# mos.net
KiCad netlist of a schematic drawn in Altium Designer
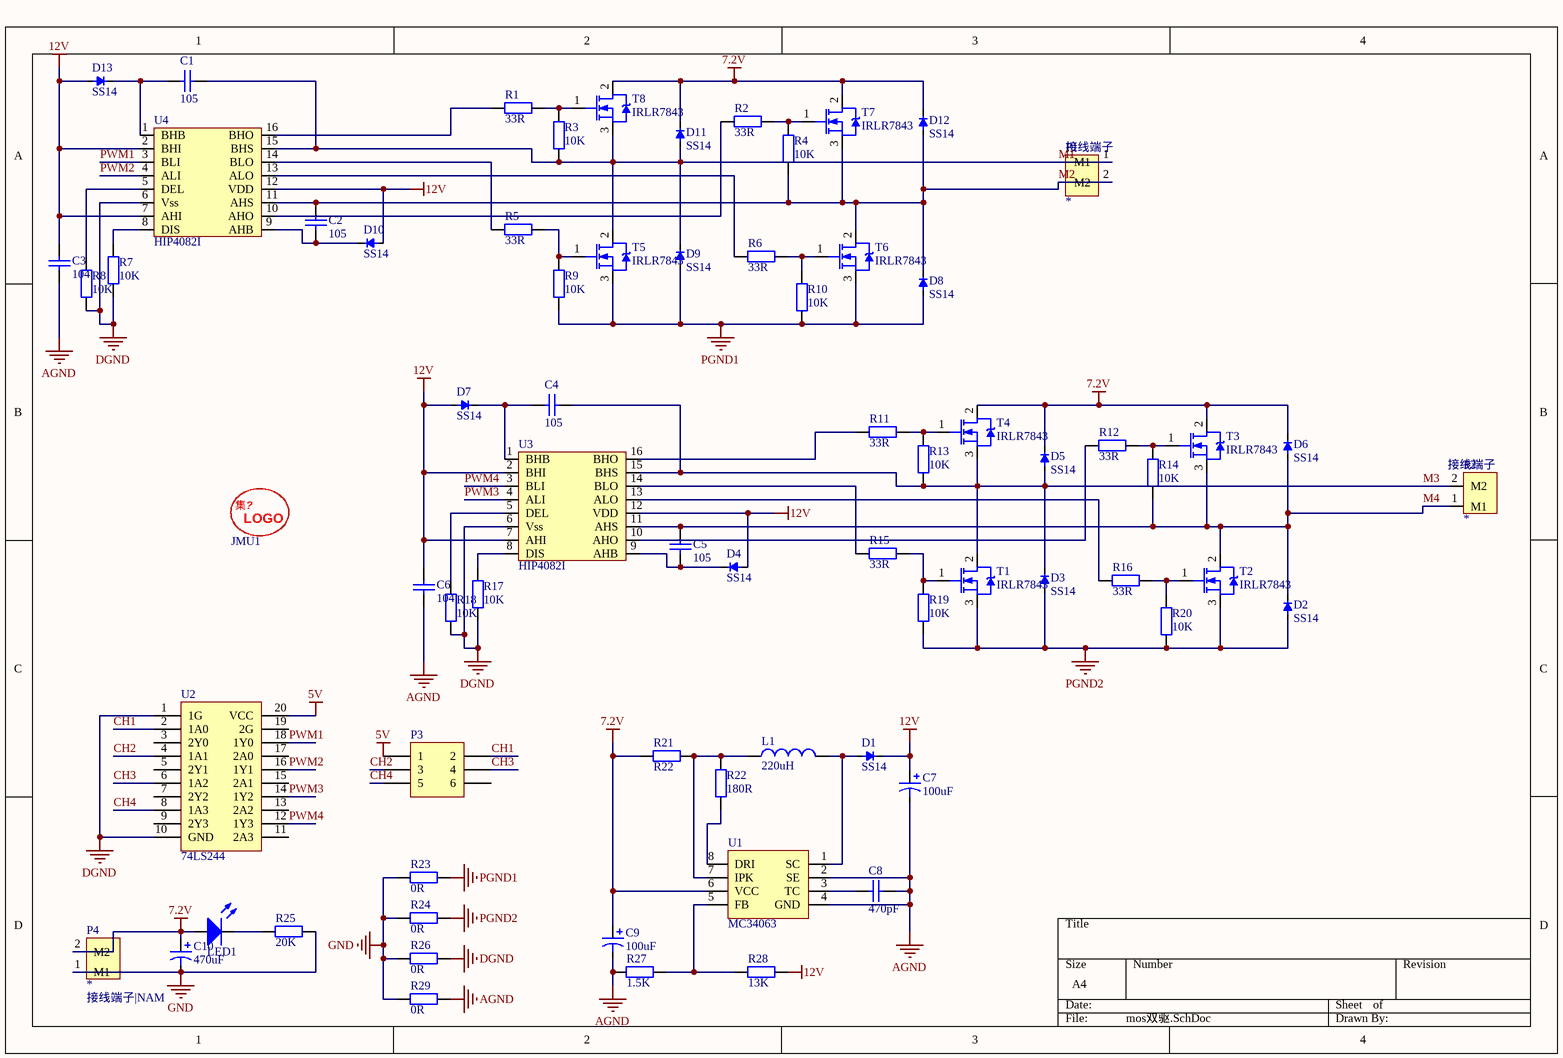
[diagram p0: mos双驱.SchDoc]

(export (version "E")
  (design (tool "Eeschema 10.0.6"))
  (components
    (comp (ref "C1")
      (value "105")
      (footprint "0805")
      (description "无极电容")
      (libsource (lib "JMU智能车专用2.0.8") (part "Cap"))
    )
    (comp (ref "C2")
      (value "105")
      (footprint "0805")
      (description "无极电容")
      (libsource (lib "JMU智能车专用2.0.8") (part "Cap"))
    )
    (comp (ref "C3")
      (value "104")
      (footprint "0805")
      (description "无极电容")
      (libsource (lib "JMU智能车专用2.0.8") (part "Cap"))
    )
    (comp (ref "C4")
      (value "105")
      (footprint "0805")
      (description "无极电容")
      (libsource (lib "JMU智能车专用2.0.8") (part "Cap"))
    )
    (comp (ref "C5")
      (value "105")
      (footprint "0805")
      (description "无极电容")
      (libsource (lib "JMU智能车专用2.0.8") (part "Cap"))
    )
    (comp (ref "C6")
      (value "104")
      (footprint "0805")
      (description "无极电容")
      (libsource (lib "JMU智能车专用2.0.8") (part "Cap"))
    )
    (comp (ref "C7")
      (value "100uF")
      (footprint "ED6.3")
      (description "通用有极电容")
      (libsource (lib "JMU智能车专用2.0.8") (part "pol cap"))
    )
    (comp (ref "C8")
      (value "470pF")
      (footprint "0805")
      (description "无极电容")
      (libsource (lib "JMU智能车专用2.0.8") (part "Cap"))
    )
    (comp (ref "C9")
      (value "100uF")
      (footprint "Pol Cap(220uF)")
      (description "通用有极电容")
      (libsource (lib "JMU智能车专用2.0.8") (part "pol cap"))
    )
    (comp (ref "C10")
      (value "470uF")
      (footprint "ED8")
      (description "ED8:470UF  ED6.3:100UF")
      (libsource (lib "JMU智能车专用2.0.8") (part "固态贴片电容"))
    )
    (comp (ref "D1") (value "SS14") (footprint "二极管") (libsource (lib "JMU智能车专用2.0.8") (part "IN5819")))
    (comp (ref "D2") (value "SS14") (footprint "二极管") (libsource (lib "JMU智能车专用2.0.8") (part "IN5819")))
    (comp (ref "D3") (value "SS14") (footprint "二极管") (libsource (lib "JMU智能车专用2.0.8") (part "IN5819")))
    (comp (ref "D4") (value "SS14") (footprint "二极管") (libsource (lib "JMU智能车专用2.0.8") (part "IN5819")))
    (comp (ref "D5") (value "SS14") (footprint "二极管") (libsource (lib "JMU智能车专用2.0.8") (part "IN5819")))
    (comp (ref "D6") (value "SS14") (footprint "二极管") (libsource (lib "JMU智能车专用2.0.8") (part "IN5819")))
    (comp (ref "D7") (value "SS14") (footprint "二极管") (libsource (lib "JMU智能车专用2.0.8") (part "IN5819")))
    (comp (ref "D8") (value "SS14") (footprint "二极管") (libsource (lib "JMU智能车专用2.0.8") (part "IN5819")))
    (comp (ref "D9") (value "SS14") (footprint "二极管") (libsource (lib "JMU智能车专用2.0.8") (part "IN5819")))
    (comp (ref "D10") (value "SS14") (footprint "二极管") (libsource (lib "JMU智能车专用2.0.8") (part "IN5819")))
    (comp (ref "D11") (value "SS14") (footprint "二极管") (libsource (lib "JMU智能车专用2.0.8") (part "IN5819")))
    (comp (ref "D12") (value "SS14") (footprint "二极管") (libsource (lib "JMU智能车专用2.0.8") (part "IN5819")))
    (comp (ref "D13") (value "SS14") (footprint "二极管") (libsource (lib "JMU智能车专用2.0.8") (part "IN5819")))
    (comp (ref "JMU1")
      (value "JMU")
      (footprint "JMU_logo（1）")
      (libsource (lib "JMU智能车专用2.0.8") (part "JMU-LOGO"))
    )
    (comp (ref "L1")
      (value "220uH")
      (footprint "电感（220uh）")
      (description "7*7*4")
      (libsource (lib "JMU智能车专用2.0.8") (part "电感 220uh"))
    )
    (comp (ref "LED1")
      (value "LED")
      (footprint "LED(0805)")
      (description "发光二极管")
      (libsource (lib "JMU智能车专用2.0.8") (part "LED"))
    )
    (comp (ref "P1") (value "*") (footprint "接线端子") (libsource (lib "") (part "接线端子_1")))
    (comp (ref "P2") (value "*") (footprint "接线端子") (libsource (lib "JMU智能车专用2.0.8") (part "接线端子")))
    (comp (ref "P3")
      (value "Header 3X2")
      (footprint "HDR2X3")
      (description "Header, 3-Pin, Dual row")
      (fields (field (name "PUBLISHER") "Altium Limited"))
      (libsource (lib "Miscellaneous Connectors") (part "Header 3X2"))
    )
    (comp (ref "P4")
      (value "*")
      (footprint "接线端子")
      (fields (field (name "ALTIUM_UNNAMED_3") "接线端子"))
      (libsource (lib "JMU智能车专用2.0.8") (part "接线端子"))
    )
    (comp (ref "R1")
      (value "33R")
      (footprint "0603")
      (description "通用电阻")
      (libsource (lib "") (part "Res_2"))
    )
    (comp (ref "R2")
      (value "33R")
      (footprint "0603")
      (description "通用电阻")
      (libsource (lib "") (part "Res_2"))
    )
    (comp (ref "R3")
      (value "10K")
      (footprint "0603")
      (description "通用电阻")
      (libsource (lib "JMU智能车专用2.0.8") (part "Res"))
    )
    (comp (ref "R4")
      (value "10K")
      (footprint "0603")
      (description "通用电阻")
      (libsource (lib "JMU智能车专用2.0.8") (part "Res"))
    )
    (comp (ref "R5")
      (value "33R")
      (footprint "0603")
      (description "通用电阻")
      (libsource (lib "") (part "Res_2"))
    )
    (comp (ref "R6")
      (value "33R")
      (footprint "0603")
      (description "通用电阻")
      (libsource (lib "") (part "Res_2"))
    )
    (comp (ref "R7")
      (value "10K")
      (footprint "0603")
      (description "通用电阻")
      (libsource (lib "JMU智能车专用2.0.8") (part "Res"))
    )
    (comp (ref "R8")
      (value "10K")
      (footprint "0603")
      (description "通用电阻")
      (libsource (lib "JMU智能车专用2.0.8") (part "Res"))
    )
    (comp (ref "R9")
      (value "10K")
      (footprint "0603")
      (description "通用电阻")
      (libsource (lib "JMU智能车专用2.0.8") (part "Res"))
    )
    (comp (ref "R10")
      (value "10K")
      (footprint "0603")
      (description "通用电阻")
      (libsource (lib "JMU智能车专用2.0.8") (part "Res"))
    )
    (comp (ref "R11")
      (value "33R")
      (footprint "0603")
      (description "通用电阻")
      (libsource (lib "") (part "Res_2"))
    )
    (comp (ref "R12")
      (value "33R")
      (footprint "0603")
      (description "通用电阻")
      (libsource (lib "") (part "Res_2"))
    )
    (comp (ref "R13")
      (value "10K")
      (footprint "0603")
      (description "通用电阻")
      (libsource (lib "JMU智能车专用2.0.8") (part "Res"))
    )
    (comp (ref "R14")
      (value "10K")
      (footprint "0603")
      (description "通用电阻")
      (libsource (lib "JMU智能车专用2.0.8") (part "Res"))
    )
    (comp (ref "R15")
      (value "33R")
      (footprint "0603")
      (description "通用电阻")
      (libsource (lib "") (part "Res_2"))
    )
    (comp (ref "R16")
      (value "33R")
      (footprint "0603")
      (description "通用电阻")
      (libsource (lib "") (part "Res_2"))
    )
    (comp (ref "R17")
      (value "10K")
      (footprint "0603")
      (description "通用电阻")
      (libsource (lib "JMU智能车专用2.0.8") (part "Res"))
    )
    (comp (ref "R18")
      (value "10K")
      (footprint "0603")
      (description "通用电阻")
      (libsource (lib "JMU智能车专用2.0.8") (part "Res"))
    )
    (comp (ref "R19")
      (value "10K")
      (footprint "0603")
      (description "通用电阻")
      (libsource (lib "JMU智能车专用2.0.8") (part "Res"))
    )
    (comp (ref "R20")
      (value "10K")
      (footprint "0603")
      (description "通用电阻")
      (libsource (lib "JMU智能车专用2.0.8") (part "Res"))
    )
    (comp (ref "R21")
      (value "R22")
      (footprint "0805")
      (description "通用电阻")
      (libsource (lib "") (part "Res_2"))
    )
    (comp (ref "R22")
      (value "180R")
      (footprint "0805")
      (description "通用电阻")
      (libsource (lib "JMU智能车专用2.0.8") (part "Res"))
    )
    (comp (ref "R23")
      (value "0R")
      (footprint "0805")
      (description "通用电阻")
      (libsource (lib "") (part "Res_1"))
    )
    (comp (ref "R24")
      (value "0R")
      (footprint "0805")
      (description "通用电阻")
      (libsource (lib "") (part "Res_1"))
    )
    (comp (ref "R25")
      (value "20K")
      (footprint "0805")
      (description "通用电阻")
      (libsource (lib "") (part "Res_1"))
    )
    (comp (ref "R26")
      (value "0R")
      (footprint "0805")
      (description "通用电阻")
      (libsource (lib "") (part "Res_1"))
    )
    (comp (ref "R27")
      (value "1.5K")
      (footprint "0805")
      (description "通用电阻")
      (libsource (lib "") (part "Res_1"))
    )
    (comp (ref "R28")
      (value "13K")
      (footprint "0805")
      (description "通用电阻")
      (libsource (lib "") (part "Res_1"))
    )
    (comp (ref "R29")
      (value "0R")
      (footprint "0805")
      (description "通用电阻")
      (libsource (lib "") (part "Res_1"))
    )
    (comp (ref "T1")
      (value "IRLR7843")
      (footprint "IRLR7843(MOS)")
      (libsource (lib "JMU智能车专用2.0.8") (part "N_MOS(IRLR7843)"))
    )
    (comp (ref "T2")
      (value "IRLR7843")
      (footprint "IRLR7843(MOS)")
      (libsource (lib "JMU智能车专用2.0.8") (part "N_MOS(IRLR7843)"))
    )
    (comp (ref "T3")
      (value "IRLR7843")
      (footprint "IRLR7843(MOS)")
      (libsource (lib "JMU智能车专用2.0.8") (part "N_MOS(IRLR7843)"))
    )
    (comp (ref "T4")
      (value "IRLR7843")
      (footprint "IRLR7843(MOS)")
      (libsource (lib "JMU智能车专用2.0.8") (part "N_MOS(IRLR7843)"))
    )
    (comp (ref "T5")
      (value "IRLR7843")
      (footprint "IRLR7843(MOS)")
      (libsource (lib "JMU智能车专用2.0.8") (part "N_MOS(IRLR7843)"))
    )
    (comp (ref "T6")
      (value "IRLR7843")
      (footprint "IRLR7843(MOS)")
      (libsource (lib "JMU智能车专用2.0.8") (part "N_MOS(IRLR7843)"))
    )
    (comp (ref "T7")
      (value "IRLR7843")
      (footprint "IRLR7843(MOS)")
      (libsource (lib "JMU智能车专用2.0.8") (part "N_MOS(IRLR7843)"))
    )
    (comp (ref "T8")
      (value "IRLR7843")
      (footprint "IRLR7843(MOS)")
      (libsource (lib "JMU智能车专用2.0.8") (part "N_MOS(IRLR7843)"))
    )
    (comp (ref "U1")
      (value "MC34063")
      (footprint "MA34063")
      (libsource (lib "JMU智能车专用2.0.8") (part "MC34063"))
    )
    (comp (ref "U2")
      (value "74LS244")
      (footprint "74LS244D")
      (libsource (lib "JMU智能车专用2.0.8") (part "74LS244"))
    )
    (comp (ref "U3")
      (value "HIP4082I")
      (footprint "HIP4082I")
      (libsource (lib "JMU智能车专用2.0.8") (part "HIP4082I"))
    )
    (comp (ref "U4")
      (value "HIP4082I")
      (footprint "HIP4082I")
      (libsource (lib "JMU智能车专用2.0.8") (part "HIP4082I"))
    )
  )
  (nets
    (net (code "1") (name "/CH1") (class "Default")
      (node (ref "P3") (pin "2") (pinfunction "2_2") (pintype "passive"))
      (node (ref "U2") (pin "2") (pinfunction "1A0_2") (pintype "passive"))
    )
    (net (code "2") (name "/CH2") (class "Default")
      (node (ref "P3") (pin "3") (pinfunction "3_3") (pintype "passive"))
      (node (ref "U2") (pin "4") (pinfunction "1A1_4") (pintype "passive"))
    )
    (net (code "3") (name "/CH3") (class "Default")
      (node (ref "P3") (pin "4") (pinfunction "4_4") (pintype "passive"))
      (node (ref "U2") (pin "6") (pinfunction "1A2_6") (pintype "passive"))
    )
    (net (code "4") (name "/CH4") (class "Default")
      (node (ref "P3") (pin "5") (pinfunction "5_5") (pintype "passive"))
      (node (ref "U2") (pin "8") (pinfunction "1A3_8") (pintype "passive"))
    )
    (net (code "5") (name "/M1") (class "Default")
      (node (ref "C1") (pin "2") (pinfunction "2_2") (pintype "passive"))
      (node (ref "D11") (pin "1") (pinfunction "+_1") (pintype "passive"))
      (node (ref "D9") (pin "2") (pinfunction "-_2") (pintype "passive"))
      (node (ref "P1") (pin "1") (pinfunction "M1_1") (pintype "passive"))
      (node (ref "R3") (pin "1") (pinfunction "1_1") (pintype "passive"))
      (node (ref "T5") (pin "2") (pinfunction "D_2") (pintype "passive"))
      (node (ref "T8") (pin "3") (pinfunction "S_3") (pintype "passive"))
      (node (ref "U4") (pin "15") (pinfunction "BHS_15") (pintype "passive"))
    )
    (net (code "6") (name "/M2") (class "Default")
      (node (ref "C2") (pin "2") (pinfunction "2_2") (pintype "passive"))
      (node (ref "D12") (pin "1") (pinfunction "+_1") (pintype "passive"))
      (node (ref "D8") (pin "2") (pinfunction "-_2") (pintype "passive"))
      (node (ref "P1") (pin "2") (pinfunction "M2_2") (pintype "passive"))
      (node (ref "R4") (pin "1") (pinfunction "1_1") (pintype "passive"))
      (node (ref "T6") (pin "2") (pinfunction "D_2") (pintype "passive"))
      (node (ref "T7") (pin "3") (pinfunction "S_3") (pintype "passive"))
      (node (ref "U4") (pin "11") (pinfunction "AHS_11") (pintype "passive"))
    )
    (net (code "7") (name "/M3") (class "Default")
      (node (ref "C4") (pin "2") (pinfunction "2_2") (pintype "passive"))
      (node (ref "D3") (pin "2") (pinfunction "-_2") (pintype "passive"))
      (node (ref "D5") (pin "1") (pinfunction "+_1") (pintype "passive"))
      (node (ref "P2") (pin "2") (pinfunction "M2_2") (pintype "passive"))
      (node (ref "R13") (pin "1") (pinfunction "1_1") (pintype "passive"))
      (node (ref "T1") (pin "2") (pinfunction "D_2") (pintype "passive"))
      (node (ref "T4") (pin "3") (pinfunction "S_3") (pintype "passive"))
      (node (ref "U3") (pin "15") (pinfunction "BHS_15") (pintype "passive"))
    )
    (net (code "8") (name "/M4") (class "Default")
      (node (ref "C5") (pin "2") (pinfunction "2_2") (pintype "passive"))
      (node (ref "D2") (pin "2") (pinfunction "-_2") (pintype "passive"))
      (node (ref "D6") (pin "1") (pinfunction "+_1") (pintype "passive"))
      (node (ref "P2") (pin "1") (pinfunction "M1_1") (pintype "passive"))
      (node (ref "R14") (pin "1") (pinfunction "1_1") (pintype "passive"))
      (node (ref "T2") (pin "2") (pinfunction "D_2") (pintype "passive"))
      (node (ref "T3") (pin "3") (pinfunction "S_3") (pintype "passive"))
      (node (ref "U3") (pin "11") (pinfunction "AHS_11") (pintype "passive"))
    )
    (net (code "9") (name "/PWM1") (class "Default")
      (node (ref "U2") (pin "18") (pinfunction "1Y0_18") (pintype "passive"))
      (node (ref "U4") (pin "3") (pinfunction "BLI_3") (pintype "passive"))
    )
    (net (code "10") (name "/PWM2") (class "Default")
      (node (ref "U2") (pin "16") (pinfunction "1Y1_16") (pintype "passive"))
      (node (ref "U4") (pin "4") (pinfunction "ALI_4") (pintype "passive"))
    )
    (net (code "11") (name "/PWM3") (class "Default")
      (node (ref "U2") (pin "14") (pinfunction "1Y2_14") (pintype "passive"))
      (node (ref "U3") (pin "4") (pinfunction "ALI_4") (pintype "passive"))
    )
    (net (code "12") (name "/PWM4") (class "Default")
      (node (ref "U2") (pin "12") (pinfunction "1Y3_12") (pintype "passive"))
      (node (ref "U3") (pin "3") (pinfunction "BLI_3") (pintype "passive"))
    )
    (net (code "13") (name "5V") (class "Default")
      (node (ref "P3") (pin "1") (pinfunction "1_1") (pintype "passive"))
      (node (ref "U2") (pin "20") (pinfunction "VCC_20") (pintype "passive"))
    )
    (net (code "14") (name "7.2V") (class "Default")
      (node (ref "C10") (pin "1") (pinfunction "1_1") (pintype "passive"))
      (node (ref "C9") (pin "1") (pinfunction "1_1") (pintype "passive"))
      (node (ref "D11") (pin "2") (pinfunction "-_2") (pintype "passive"))
      (node (ref "D12") (pin "2") (pinfunction "-_2") (pintype "passive"))
      (node (ref "D5") (pin "2") (pinfunction "-_2") (pintype "passive"))
      (node (ref "D6") (pin "2") (pinfunction "-_2") (pintype "passive"))
      (node (ref "LED1") (pin "1") (pinfunction "A_1") (pintype "passive"))
      (node (ref "P4") (pin "2") (pinfunction "M2_2") (pintype "passive"))
      (node (ref "R21") (pin "2") (pinfunction "2_2") (pintype "passive"))
      (node (ref "T3") (pin "2") (pinfunction "D_2") (pintype "passive"))
      (node (ref "T4") (pin "2") (pinfunction "D_2") (pintype "passive"))
      (node (ref "T7") (pin "2") (pinfunction "D_2") (pintype "passive"))
      (node (ref "T8") (pin "2") (pinfunction "D_2") (pintype "passive"))
      (node (ref "U1") (pin "6") (pinfunction "VCC_6") (pintype "passive"))
    )
    (net (code "15") (name "12V") (class "Default")
      (node (ref "C3") (pin "2") (pinfunction "2_2") (pintype "passive"))
      (node (ref "C6") (pin "2") (pinfunction "2_2") (pintype "passive"))
      (node (ref "C7") (pin "1") (pinfunction "1_1") (pintype "passive"))
      (node (ref "D1") (pin "2") (pinfunction "-_2") (pintype "passive"))
      (node (ref "D10") (pin "1") (pinfunction "+_1") (pintype "passive"))
      (node (ref "D13") (pin "1") (pinfunction "+_1") (pintype "passive"))
      (node (ref "D4") (pin "1") (pinfunction "+_1") (pintype "passive"))
      (node (ref "D7") (pin "1") (pinfunction "+_1") (pintype "passive"))
      (node (ref "R28") (pin "2") (pinfunction "2_2") (pintype "passive"))
      (node (ref "U3") (pin "12") (pinfunction "VDD_12") (pintype "passive"))
      (node (ref "U3") (pin "2") (pinfunction "BHI_2") (pintype "passive"))
      (node (ref "U3") (pin "7") (pinfunction "AHI_7") (pintype "passive"))
      (node (ref "U4") (pin "12") (pinfunction "VDD_12") (pintype "passive"))
      (node (ref "U4") (pin "2") (pinfunction "BHI_2") (pintype "passive"))
      (node (ref "U4") (pin "7") (pinfunction "AHI_7") (pintype "passive"))
    )
    (net (code "16") (name "AGND") (class "Default")
      (node (ref "C3") (pin "1") (pinfunction "1_1") (pintype "passive"))
      (node (ref "C6") (pin "1") (pinfunction "1_1") (pintype "passive"))
      (node (ref "C7") (pin "2") (pinfunction "2_2") (pintype "passive"))
      (node (ref "C8") (pin "1") (pinfunction "1_1") (pintype "passive"))
      (node (ref "C9") (pin "2") (pinfunction "2_2") (pintype "passive"))
      (node (ref "R27") (pin "1") (pinfunction "1_1") (pintype "passive"))
      (node (ref "R29") (pin "2") (pinfunction "2_2") (pintype "passive"))
      (node (ref "U1") (pin "2") (pinfunction "SE_2") (pintype "passive"))
      (node (ref "U1") (pin "4") (pinfunction "GND_4") (pintype "passive"))
    )
    (net (code "17") (name "DGND") (class "Default")
      (node (ref "R17") (pin "1") (pinfunction "1_1") (pintype "passive"))
      (node (ref "R18") (pin "1") (pinfunction "1_1") (pintype "passive"))
      (node (ref "R26") (pin "2") (pinfunction "2_2") (pintype "passive"))
      (node (ref "R7") (pin "1") (pinfunction "1_1") (pintype "passive"))
      (node (ref "R8") (pin "1") (pinfunction "1_1") (pintype "passive"))
      (node (ref "U2") (pin "1") (pinfunction "1G_1") (pintype "passive"))
      (node (ref "U2") (pin "10") (pinfunction "GND_10") (pintype "passive"))
      (node (ref "U3") (pin "6") (pinfunction "Vss_6") (pintype "passive"))
      (node (ref "U4") (pin "6") (pinfunction "Vss_6") (pintype "passive"))
    )
    (net (code "18") (name "GND") (class "Default")
      (node (ref "C10") (pin "2") (pinfunction "2_2") (pintype "passive"))
      (node (ref "P4") (pin "1") (pinfunction "M1_1") (pintype "passive"))
      (node (ref "R23") (pin "1") (pinfunction "1_1") (pintype "passive"))
      (node (ref "R24") (pin "1") (pinfunction "1_1") (pintype "passive"))
      (node (ref "R25") (pin "2") (pinfunction "2_2") (pintype "passive"))
      (node (ref "R26") (pin "1") (pinfunction "1_1") (pintype "passive"))
      (node (ref "R29") (pin "1") (pinfunction "1_1") (pintype "passive"))
    )
    (net (code "19") (name "Net-(D1-+)") (class "Default")
      (node (ref "D1") (pin "1") (pinfunction "+_1") (pintype "passive"))
      (node (ref "L1") (pin "2") (pinfunction "2_2") (pintype "passive"))
      (node (ref "U1") (pin "1") (pinfunction "SC_1") (pintype "passive"))
    )
    (net (code "20") (name "Net-(D4--)") (class "Default")
      (node (ref "C5") (pin "1") (pinfunction "1_1") (pintype "passive"))
      (node (ref "D4") (pin "2") (pinfunction "-_2") (pintype "passive"))
      (node (ref "U3") (pin "9") (pinfunction "AHB_9") (pintype "passive"))
    )
    (net (code "21") (name "Net-(D7--)") (class "Default")
      (node (ref "C4") (pin "1") (pinfunction "1_1") (pintype "passive"))
      (node (ref "D7") (pin "2") (pinfunction "-_2") (pintype "passive"))
      (node (ref "U3") (pin "1") (pinfunction "BHB_1") (pintype "passive"))
    )
    (net (code "22") (name "Net-(D10--)") (class "Default")
      (node (ref "C2") (pin "1") (pinfunction "1_1") (pintype "passive"))
      (node (ref "D10") (pin "2") (pinfunction "-_2") (pintype "passive"))
      (node (ref "U4") (pin "9") (pinfunction "AHB_9") (pintype "passive"))
    )
    (net (code "23") (name "Net-(D13--)") (class "Default")
      (node (ref "C1") (pin "1") (pinfunction "1_1") (pintype "passive"))
      (node (ref "D13") (pin "2") (pinfunction "-_2") (pintype "passive"))
      (node (ref "U4") (pin "1") (pinfunction "BHB_1") (pintype "passive"))
    )
    (net (code "24") (name "Net-(LED1-K)") (class "Default")
      (node (ref "LED1") (pin "2") (pinfunction "K_2") (pintype "passive"))
      (node (ref "R25") (pin "1") (pinfunction "1_1") (pintype "passive"))
    )
    (net (code "25") (name "Net-(T1-G)") (class "Default")
      (node (ref "R15") (pin "1") (pinfunction "1_1") (pintype "passive"))
      (node (ref "R19") (pin "2") (pinfunction "2_2") (pintype "passive"))
      (node (ref "T1") (pin "1") (pinfunction "G_1") (pintype "passive"))
    )
    (net (code "26") (name "Net-(T2-G)") (class "Default")
      (node (ref "R16") (pin "1") (pinfunction "1_1") (pintype "passive"))
      (node (ref "R20") (pin "2") (pinfunction "2_2") (pintype "passive"))
      (node (ref "T2") (pin "1") (pinfunction "G_1") (pintype "passive"))
    )
    (net (code "27") (name "Net-(T3-G)") (class "Default")
      (node (ref "R12") (pin "1") (pinfunction "1_1") (pintype "passive"))
      (node (ref "R14") (pin "2") (pinfunction "2_2") (pintype "passive"))
      (node (ref "T3") (pin "1") (pinfunction "G_1") (pintype "passive"))
    )
    (net (code "28") (name "Net-(T4-G)") (class "Default")
      (node (ref "R11") (pin "1") (pinfunction "1_1") (pintype "passive"))
      (node (ref "R13") (pin "2") (pinfunction "2_2") (pintype "passive"))
      (node (ref "T4") (pin "1") (pinfunction "G_1") (pintype "passive"))
    )
    (net (code "29") (name "Net-(T5-G)") (class "Default")
      (node (ref "R5") (pin "1") (pinfunction "1_1") (pintype "passive"))
      (node (ref "R9") (pin "2") (pinfunction "2_2") (pintype "passive"))
      (node (ref "T5") (pin "1") (pinfunction "G_1") (pintype "passive"))
    )
    (net (code "30") (name "Net-(T6-G)") (class "Default")
      (node (ref "R10") (pin "2") (pinfunction "2_2") (pintype "passive"))
      (node (ref "R6") (pin "1") (pinfunction "1_1") (pintype "passive"))
      (node (ref "T6") (pin "1") (pinfunction "G_1") (pintype "passive"))
    )
    (net (code "31") (name "Net-(T7-G)") (class "Default")
      (node (ref "R2") (pin "1") (pinfunction "1_1") (pintype "passive"))
      (node (ref "R4") (pin "2") (pinfunction "2_2") (pintype "passive"))
      (node (ref "T7") (pin "1") (pinfunction "G_1") (pintype "passive"))
    )
    (net (code "32") (name "Net-(T8-G)") (class "Default")
      (node (ref "R1") (pin "1") (pinfunction "1_1") (pintype "passive"))
      (node (ref "R3") (pin "2") (pinfunction "2_2") (pintype "passive"))
      (node (ref "T8") (pin "1") (pinfunction "G_1") (pintype "passive"))
    )
    (net (code "33") (name "Net-(U1-DRI)") (class "Default")
      (node (ref "R22") (pin "1") (pinfunction "1_1") (pintype "passive"))
      (node (ref "U1") (pin "8") (pinfunction "DRI_8") (pintype "passive"))
    )
    (net (code "34") (name "Net-(U1-FB)") (class "Default")
      (node (ref "R27") (pin "2") (pinfunction "2_2") (pintype "passive"))
      (node (ref "R28") (pin "1") (pinfunction "1_1") (pintype "passive"))
      (node (ref "U1") (pin "5") (pinfunction "FB_5") (pintype "passive"))
    )
    (net (code "35") (name "Net-(U1-IPK)") (class "Default")
      (node (ref "L1") (pin "1") (pinfunction "1_1") (pintype "passive"))
      (node (ref "R21") (pin "1") (pinfunction "1_1") (pintype "passive"))
      (node (ref "R22") (pin "2") (pinfunction "2_2") (pintype "passive"))
      (node (ref "U1") (pin "7") (pinfunction "IPK_7") (pintype "passive"))
    )
    (net (code "36") (name "Net-(U1-TC)") (class "Default")
      (node (ref "C8") (pin "2") (pinfunction "2_2") (pintype "passive"))
      (node (ref "U1") (pin "3") (pinfunction "TC_3") (pintype "passive"))
    )
    (net (code "37") (name "Net-(U3-AHO)") (class "Default")
      (node (ref "R12") (pin "2") (pinfunction "2_2") (pintype "passive"))
      (node (ref "U3") (pin "10") (pinfunction "AHO_10") (pintype "passive"))
    )
    (net (code "38") (name "Net-(U3-ALO)") (class "Default")
      (node (ref "R16") (pin "2") (pinfunction "2_2") (pintype "passive"))
      (node (ref "U3") (pin "13") (pinfunction "ALO_13") (pintype "passive"))
    )
    (net (code "39") (name "Net-(U3-BHO)") (class "Default")
      (node (ref "R11") (pin "2") (pinfunction "2_2") (pintype "passive"))
      (node (ref "U3") (pin "16") (pinfunction "BHO_16") (pintype "passive"))
    )
    (net (code "40") (name "Net-(U3-BLO)") (class "Default")
      (node (ref "R15") (pin "2") (pinfunction "2_2") (pintype "passive"))
      (node (ref "U3") (pin "14") (pinfunction "BLO_14") (pintype "passive"))
    )
    (net (code "41") (name "Net-(U3-DEL)") (class "Default")
      (node (ref "R18") (pin "2") (pinfunction "2_2") (pintype "passive"))
      (node (ref "U3") (pin "5") (pinfunction "DEL_5") (pintype "passive"))
    )
    (net (code "42") (name "Net-(U3-DIS)") (class "Default")
      (node (ref "R17") (pin "2") (pinfunction "2_2") (pintype "passive"))
      (node (ref "U3") (pin "8") (pinfunction "DIS_8") (pintype "passive"))
    )
    (net (code "43") (name "Net-(U4-AHO)") (class "Default")
      (node (ref "R2") (pin "2") (pinfunction "2_2") (pintype "passive"))
      (node (ref "U4") (pin "10") (pinfunction "AHO_10") (pintype "passive"))
    )
    (net (code "44") (name "Net-(U4-ALO)") (class "Default")
      (node (ref "R6") (pin "2") (pinfunction "2_2") (pintype "passive"))
      (node (ref "U4") (pin "13") (pinfunction "ALO_13") (pintype "passive"))
    )
    (net (code "45") (name "Net-(U4-BHO)") (class "Default")
      (node (ref "R1") (pin "2") (pinfunction "2_2") (pintype "passive"))
      (node (ref "U4") (pin "16") (pinfunction "BHO_16") (pintype "passive"))
    )
    (net (code "46") (name "Net-(U4-BLO)") (class "Default")
      (node (ref "R5") (pin "2") (pinfunction "2_2") (pintype "passive"))
      (node (ref "U4") (pin "14") (pinfunction "BLO_14") (pintype "passive"))
    )
    (net (code "47") (name "Net-(U4-DEL)") (class "Default")
      (node (ref "R8") (pin "2") (pinfunction "2_2") (pintype "passive"))
      (node (ref "U4") (pin "5") (pinfunction "DEL_5") (pintype "passive"))
    )
    (net (code "48") (name "Net-(U4-DIS)") (class "Default")
      (node (ref "R7") (pin "2") (pinfunction "2_2") (pintype "passive"))
      (node (ref "U4") (pin "8") (pinfunction "DIS_8") (pintype "passive"))
    )
    (net (code "49") (name "PGND1") (class "Default")
      (node (ref "D8") (pin "1") (pinfunction "+_1") (pintype "passive"))
      (node (ref "D9") (pin "1") (pinfunction "+_1") (pintype "passive"))
      (node (ref "R10") (pin "1") (pinfunction "1_1") (pintype "passive"))
      (node (ref "R23") (pin "2") (pinfunction "2_2") (pintype "passive"))
      (node (ref "R9") (pin "1") (pinfunction "1_1") (pintype "passive"))
      (node (ref "T5") (pin "3") (pinfunction "S_3") (pintype "passive"))
      (node (ref "T6") (pin "3") (pinfunction "S_3") (pintype "passive"))
    )
    (net (code "50") (name "PGND2") (class "Default")
      (node (ref "D2") (pin "1") (pinfunction "+_1") (pintype "passive"))
      (node (ref "D3") (pin "1") (pinfunction "+_1") (pintype "passive"))
      (node (ref "R19") (pin "1") (pinfunction "1_1") (pintype "passive"))
      (node (ref "R20") (pin "1") (pinfunction "1_1") (pintype "passive"))
      (node (ref "R24") (pin "2") (pinfunction "2_2") (pintype "passive"))
      (node (ref "T1") (pin "3") (pinfunction "S_3") (pintype "passive"))
      (node (ref "T2") (pin "3") (pinfunction "S_3") (pintype "passive"))
    )
    (net (code "51") (name "unconnected-(P3-Pad6)") (class "Default")
      (node (ref "P3") (pin "6") (pinfunction "6_6") (pintype "passive"))
    )
    (net (code "52") (name "unconnected-(U2-2A0-Pad17)") (class "Default")
      (node (ref "U2") (pin "17") (pinfunction "2A0_17") (pintype "passive"))
    )
    (net (code "53") (name "unconnected-(U2-2A1-Pad15)") (class "Default")
      (node (ref "U2") (pin "15") (pinfunction "2A1_15") (pintype "passive"))
    )
    (net (code "54") (name "unconnected-(U2-2A2-Pad13)") (class "Default")
      (node (ref "U2") (pin "13") (pinfunction "2A2_13") (pintype "passive"))
    )
    (net (code "55") (name "unconnected-(U2-2A3-Pad11)") (class "Default")
      (node (ref "U2") (pin "11") (pinfunction "2A3_11") (pintype "passive"))
    )
    (net (code "56") (name "unconnected-(U2-2G-Pad19)") (class "Default")
      (node (ref "U2") (pin "19") (pinfunction "2G_19") (pintype "passive"))
    )
    (net (code "57") (name "unconnected-(U2-2Y0-Pad3)") (class "Default")
      (node (ref "U2") (pin "3") (pinfunction "2Y0_3") (pintype "passive"))
    )
    (net (code "58") (name "unconnected-(U2-2Y1-Pad5)") (class "Default")
      (node (ref "U2") (pin "5") (pinfunction "2Y1_5") (pintype "passive"))
    )
    (net (code "59") (name "unconnected-(U2-2Y2-Pad7)") (class "Default")
      (node (ref "U2") (pin "7") (pinfunction "2Y2_7") (pintype "passive"))
    )
    (net (code "60") (name "unconnected-(U2-2Y3-Pad9)") (class "Default")
      (node (ref "U2") (pin "9") (pinfunction "2Y3_9") (pintype "passive"))
    )
  )
)
